# LED.net
KiCad netlist of a schematic drawn in EasyEDA Pro
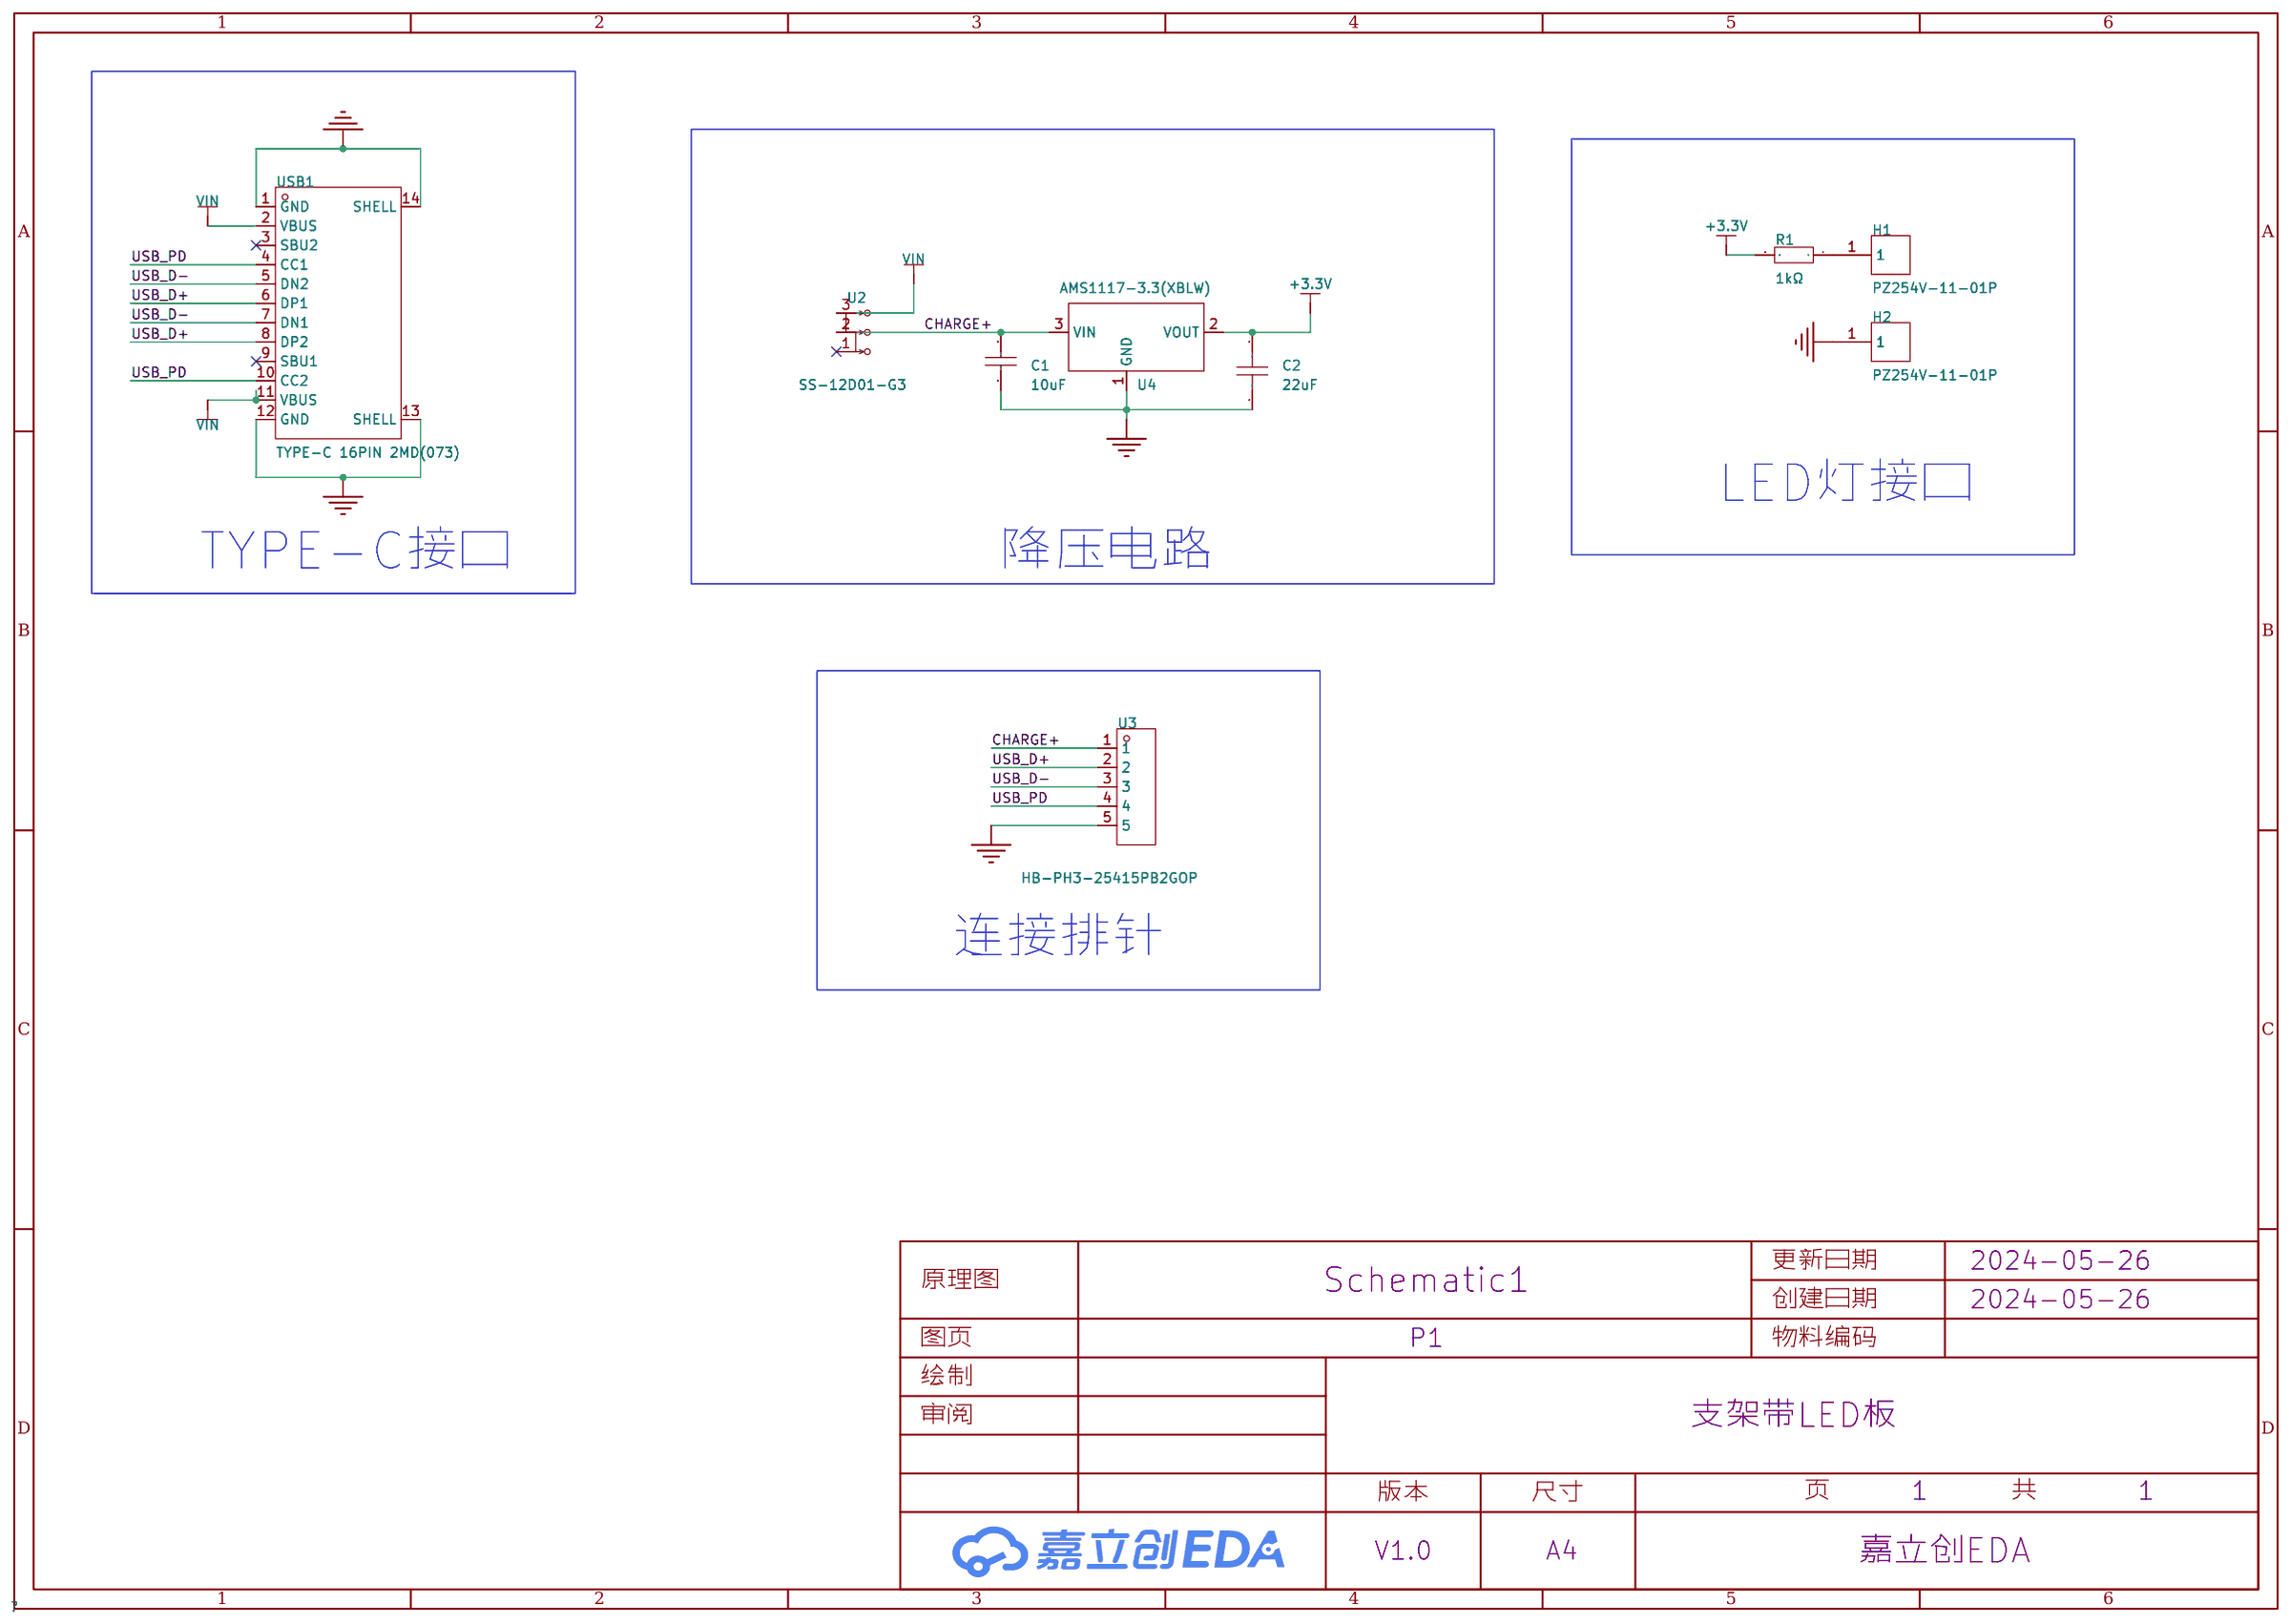
[diagram p0: schematic sheet]

(export (version "E")
  (design (tool "Eeschema 10.0.6"))
  (components
    (comp (ref "C1")
      (value "10uF")
      (footprint "easyedapro:C1210")
      (description "容值:10uF;精度:±10%;额定电压:50V;材质(温度系数):X7R;")
      (fields (field (name "Manufacturer Part") "1210B106K500NT") (field (name "Manufacturer") "FH(风华)"))
      (libsource (lib "easyedapro") (part "1210B106K500NT"))
    )
    (comp (ref "C2")
      (value "22uF")
      (footprint "easyedapro:C0603")
      (description "容值:22uF;精度:±20%;额定电压:6.3V;材质(温度系数):X5R;")
      (fields
        (field (name "Manufacturer Part") "CL10A226MQ8NRNC")
        (field (name "Manufacturer") "SAMSUNG(三星)")
      )
      (libsource (lib "easyedapro") (part "CL10A226MQ8NRNC"))
    )
    (comp (ref "H1")
      (value "PZ254V-11-01P")
      (footprint "easyedapro:HDR-TH_1P-P2.54-V-M")
      (fields (field (name "Manufacturer") "XFCN(兴飞)"))
      (libsource (lib "easyedapro") (part "PZ254V-11-01P"))
    )
    (comp (ref "H2")
      (value "PZ254V-11-01P")
      (footprint "easyedapro:HDR-TH_1P-P2.54-V-M")
      (fields (field (name "Manufacturer") "XFCN(兴飞)"))
      (libsource (lib "easyedapro") (part "PZ254V-11-01P"))
    )
    (comp (ref "R1")
      (value "1kΩ")
      (footprint "easyedapro:R0805")
      (description "电阻类型:厚膜电阻;阻值:1kΩ;精度:±1%;功率:125mW;最大工作电压:150V;温度系数:±100ppm/°C;")
      (fields (field (name "Manufacturer Part") "RC0805FR-071KL") (field (name "Manufacturer") "YAGEO(国巨)"))
      (libsource (lib "easyedapro") (part "RC0805FR-071KL"))
    )
    (comp (ref "U2")
      (value "SS-12D01-G3")
      (footprint "easyedapro:SW-TH_DEALON_SS-12D01-GX")
      (description "电路结构:单刀双掷;安装方式:直插;开关颜色:黑色;机械寿命:-;")
      (fields (field (name "Manufacturer") "DEALON(德艺隆)"))
      (libsource (lib "easyedapro") (part "SS-12D01-G3_C2998803"))
    )
    (comp (ref "U3")
      (value "HB-PH3-25415PB2GOP")
      (footprint "easyedapro:HDR-TH_5P-P2.54-V-M")
      (fields (field (name "Manufacturer") "HANBO(汉博)"))
      (libsource (lib "easyedapro") (part "HB-PH3-25415PB2GOP"))
    )
    (comp (ref "U4")
      (value "AMS1117-3.3(XBLW)")
      (footprint "easyedapro:SOT-89-3_L4.5-W2.5-P1.50-LS4.2-BR")
      (description "最大输入电压:15V;最大输出电流:1A;")
      (fields (field (name "Manufacturer") "XBLW(芯伯乐)"))
      (libsource (lib "easyedapro") (part "AMS1117-3.3(XBLW)"))
    )
    (comp (ref "USB1")
      (value "TYPE-C 16PIN 2MD(073)")
      (footprint "easyedapro:USB-C-SMD_TYPE-C-6PIN-2MD-073")
      (description "连接器类型:Type-C;标准:-;公母:母;端口数量:1;触点数量:16P;安装方式:卧贴;额定电流 - 电源:5A;工作温度范围:-25°C~+85°C;")
      (fields (field (name "Manufacturer") "SHOU HAN(首韩)"))
      (libsource (lib "easyedapro") (part "TYPE-C 16PIN 2MD(073)"))
    )
  )
  (nets
    (net (code "1") (name "+3.3V") (class "Default")
      (node (ref "C2") (pin "2") (pinfunction "2_2") (pintype "unspecified"))
      (node (ref "R1") (pin "2") (pinfunction "2_2") (pintype "input"))
      (node (ref "U4") (pin "2") (pinfunction "VOUT_2") (pintype "unspecified"))
    )
    (net (code "2") (name "/CHARGE+") (class "Default")
      (node (ref "C1") (pin "2") (pinfunction "2_2") (pintype "input"))
      (node (ref "U2") (pin "2") (pinfunction "2_2") (pintype "unspecified"))
      (node (ref "U3") (pin "1") (pinfunction "1_1") (pintype "unspecified"))
      (node (ref "U4") (pin "3") (pinfunction "VIN_3") (pintype "unspecified"))
    )
    (net (code "3") (name "/USB_D+") (class "Default")
      (node (ref "U3") (pin "2") (pinfunction "2_2") (pintype "unspecified"))
      (node (ref "USB1") (pin "6") (pinfunction "DP1_6") (pintype "unspecified"))
      (node (ref "USB1") (pin "8") (pinfunction "DP2_8") (pintype "unspecified"))
    )
    (net (code "4") (name "/USB_D-") (class "Default")
      (node (ref "U3") (pin "3") (pinfunction "3_3") (pintype "unspecified"))
      (node (ref "USB1") (pin "5") (pinfunction "DN2_5") (pintype "unspecified"))
      (node (ref "USB1") (pin "7") (pinfunction "DN1_7") (pintype "unspecified"))
    )
    (net (code "5") (name "/USB_PD") (class "Default")
      (node (ref "U3") (pin "4") (pinfunction "4_4") (pintype "unspecified"))
      (node (ref "USB1") (pin "10") (pinfunction "CC2_10") (pintype "unspecified"))
      (node (ref "USB1") (pin "4") (pinfunction "CC1_4") (pintype "unspecified"))
    )
    (net (code "6") (name "GND") (class "Default")
      (node (ref "C1") (pin "1") (pinfunction "1_1") (pintype "input"))
      (node (ref "C2") (pin "1") (pinfunction "1_1") (pintype "unspecified"))
      (node (ref "H2") (pin "1") (pinfunction "1_1") (pintype "unspecified"))
      (node (ref "U3") (pin "5") (pinfunction "5_5") (pintype "unspecified"))
      (node (ref "U4") (pin "1") (pinfunction "GND_1") (pintype "unspecified"))
      (node (ref "USB1") (pin "1") (pinfunction "GND_1") (pintype "unspecified"))
      (node (ref "USB1") (pin "12") (pinfunction "GND_12") (pintype "unspecified"))
      (node (ref "USB1") (pin "13") (pinfunction "SHELL_13") (pintype "unspecified"))
      (node (ref "USB1") (pin "14") (pinfunction "SHELL_14") (pintype "unspecified"))
    )
    (net (code "7") (name "Net-(H1-Pad1)") (class "Default")
      (node (ref "H1") (pin "1") (pinfunction "1_1") (pintype "unspecified"))
      (node (ref "R1") (pin "1") (pinfunction "1_1") (pintype "input"))
    )
    (net (code "8") (name "VIN") (class "Default")
      (node (ref "U2") (pin "3") (pinfunction "3_3") (pintype "unspecified"))
      (node (ref "USB1") (pin "11") (pinfunction "VBUS_11") (pintype "unspecified"))
      (node (ref "USB1") (pin "2") (pinfunction "VBUS_2") (pintype "unspecified"))
    )
    (net (code "9") (name "unconnected-(U2-Pad1)") (class "Default")
      (node (ref "U2") (pin "1") (pinfunction "1_1") (pintype "unspecified+no_connect"))
    )
    (net (code "10") (name "unconnected-(USB1-SBU1-Pad9)") (class "Default")
      (node (ref "USB1") (pin "9") (pinfunction "SBU1_9") (pintype "unspecified+no_connect"))
    )
    (net (code "11") (name "unconnected-(USB1-SBU2-Pad3)") (class "Default")
      (node (ref "USB1") (pin "3") (pinfunction "SBU2_3") (pintype "unspecified+no_connect"))
    )
  )
)
